# T8105.net
KiCad netlist of a schematic drawn in Altium Designer
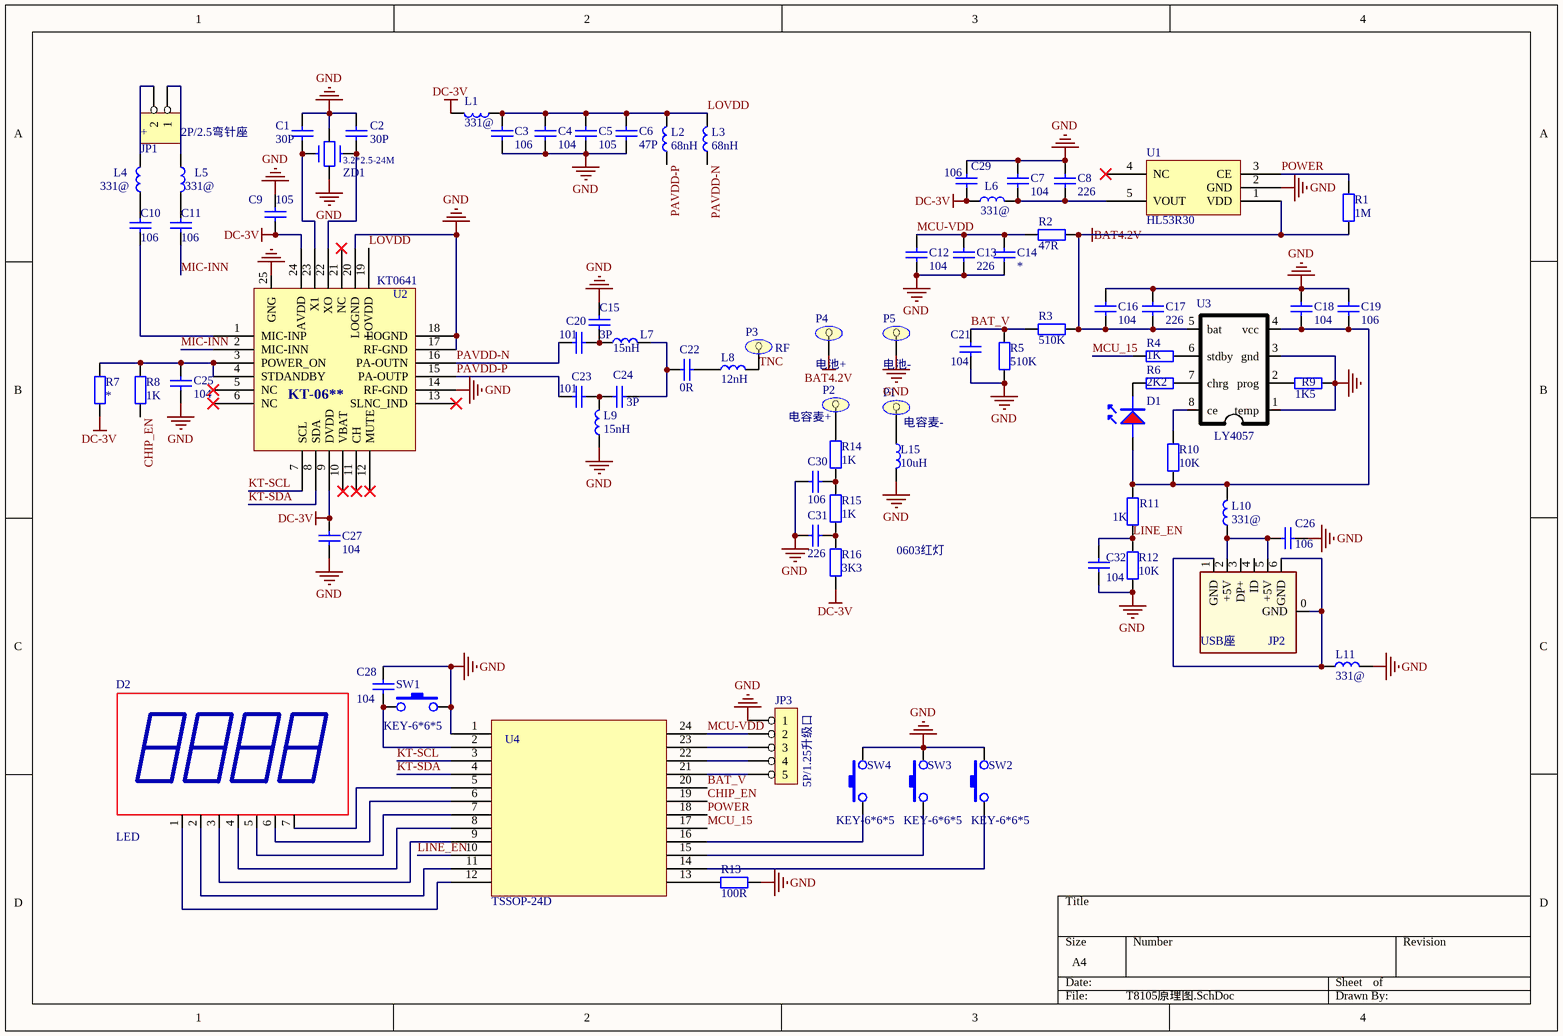
[diagram p0: T8105原理图.SchDoc]

(export (version "E")
  (design (tool "Eeschema 10.0.6"))
  (components
    (comp (ref "C1")
      (value "30P")
      (footprint "C0402")
      (description "贴片电容")
      (libsource (lib "CLR原理图封装库") (part "C0402"))
    )
    (comp (ref "C2")
      (value "30P")
      (footprint "C0402")
      (description "贴片电容")
      (libsource (lib "CLR原理图封装库") (part "C0402"))
    )
    (comp (ref "C3")
      (value "106")
      (footprint "C0603")
      (description "贴片电容")
      (libsource (lib "CLR原理图封装库") (part "C0603"))
    )
    (comp (ref "C4")
      (value "104")
      (footprint "C0402")
      (description "贴片电容")
      (libsource (lib "CLR原理图封装库") (part "C0402"))
    )
    (comp (ref "C5")
      (value "105")
      (footprint "C0402")
      (description "贴片电容")
      (libsource (lib "CLR原理图封装库") (part "C0402"))
    )
    (comp (ref "C6")
      (value "47P")
      (footprint "C0402")
      (description "贴片电容")
      (libsource (lib "CLR原理图封装库") (part "C0402"))
    )
    (comp (ref "C7")
      (value "104")
      (footprint "C0402")
      (description "贴片电容")
      (libsource (lib "CLR原理图封装库") (part "C0402"))
    )
    (comp (ref "C8")
      (value "226")
      (footprint "C0603")
      (description "贴片电容")
      (libsource (lib "CLR原理图封装库") (part "C0603"))
    )
    (comp (ref "C9")
      (value "105")
      (footprint "C0402")
      (description "贴片电容")
      (libsource (lib "CLR原理图封装库") (part "C0402"))
    )
    (comp (ref "C10")
      (value "106")
      (footprint "C0603")
      (description "贴片电容")
      (libsource (lib "CLR原理图封装库") (part "C0603"))
    )
    (comp (ref "C11")
      (value "106")
      (footprint "C0603")
      (description "贴片电容")
      (libsource (lib "CLR原理图封装库") (part "C0603"))
    )
    (comp (ref "C12")
      (value "104")
      (footprint "C0402")
      (description "贴片电容")
      (libsource (lib "CLR原理图封装库") (part "C0402"))
    )
    (comp (ref "C13")
      (value "226")
      (footprint "C0603")
      (description "贴片电容")
      (libsource (lib "CLR原理图封装库") (part "C0603"))
    )
    (comp (ref "C14")
      (value "*")
      (footprint "C1206")
      (description "贴片电容")
      (libsource (lib "CLR原理图封装库") (part "C1206"))
    )
    (comp (ref "C15")
      (value "3P")
      (footprint "C0402")
      (description "贴片电容")
      (libsource (lib "CLR原理图封装库") (part "C0402"))
    )
    (comp (ref "C16")
      (value "104")
      (footprint "C0402")
      (description "贴片电容")
      (libsource (lib "CLR原理图封装库") (part "C0402"))
    )
    (comp (ref "C17")
      (value "226")
      (footprint "C0603")
      (description "贴片电容")
      (libsource (lib "CLR原理图封装库") (part "C0603"))
    )
    (comp (ref "C18")
      (value "104")
      (footprint "C0402")
      (description "贴片电容")
      (libsource (lib "CLR原理图封装库") (part "C0402"))
    )
    (comp (ref "C19")
      (value "106")
      (footprint "C0603")
      (description "贴片电容")
      (libsource (lib "CLR原理图封装库") (part "C0603"))
    )
    (comp (ref "C20")
      (value "101")
      (footprint "C0402")
      (description "贴片电容")
      (libsource (lib "CLR原理图封装库") (part "C0402"))
    )
    (comp (ref "C21")
      (value "104")
      (footprint "C0402")
      (description "贴片电容")
      (libsource (lib "CLR原理图封装库") (part "C0402"))
    )
    (comp (ref "C22")
      (value "0R")
      (footprint "C0402")
      (description "贴片电容")
      (libsource (lib "CLR原理图封装库") (part "C0402"))
    )
    (comp (ref "C23")
      (value "101")
      (footprint "C0402")
      (description "贴片电容")
      (libsource (lib "CLR原理图封装库") (part "C0402"))
    )
    (comp (ref "C24")
      (value "3P")
      (footprint "C0402")
      (description "贴片电容")
      (libsource (lib "CLR原理图封装库") (part "C0402"))
    )
    (comp (ref "C25")
      (value "104")
      (footprint "C0402")
      (description "贴片电容")
      (libsource (lib "CLR原理图封装库") (part "C0402"))
    )
    (comp (ref "C26")
      (value "106")
      (footprint "C0603")
      (description "贴片电容")
      (libsource (lib "CLR原理图封装库") (part "C0603"))
    )
    (comp (ref "C27")
      (value "104")
      (footprint "C0402")
      (description "贴片电容")
      (libsource (lib "CLR原理图封装库") (part "C0402"))
    )
    (comp (ref "C28")
      (value "104")
      (footprint "C0402")
      (description "贴片电容")
      (libsource (lib "CLR原理图封装库") (part "C0402"))
    )
    (comp (ref "C29")
      (value "106")
      (footprint "C0603")
      (description "贴片电容")
      (libsource (lib "CLR原理图封装库") (part "C0603"))
    )
    (comp (ref "C30")
      (value "106")
      (footprint "C0603")
      (description "贴片电容")
      (libsource (lib "CLR原理图封装库") (part "C0603"))
    )
    (comp (ref "C31")
      (value "226")
      (footprint "C0603")
      (description "贴片电容")
      (libsource (lib "CLR原理图封装库") (part "C0603"))
    )
    (comp (ref "C32")
      (value "104")
      (footprint "C0402")
      (description "贴片电容")
      (libsource (lib "CLR原理图封装库") (part "C0402"))
    )
    (comp (ref "D1")
      (value "0603红灯")
      (footprint "LED-0603")
      (description "贴片LED")
      (libsource (lib "CLR原理图封装库") (part "LED-0603"))
    )
    (comp (ref "D2")
      (value "LED")
      (footprint "LED-15*16*7-7pin")
      (description "数码管")
      (libsource (lib "CLR原理图封装库") (part "LED-15*16/数码管"))
    )
    (comp (ref "JP1")
      (value "2P/2.5弯针座")
      (footprint "2P针座-2.54MM_弯针")
      (description "直插针座")
      (libsource (lib "CLR原理图封装库") (part "2P/2.5弯针座"))
    )
    (comp (ref "JP2")
      (value "USB座")
      (footprint "USB-TYPE-C3.1-6")
      (description "直插USB充电座")
      (libsource (lib "CLR原理图封装库") (part "USB-TYPE-C3.1-6"))
    )
    (comp (ref "JP3")
      (value "5P/1.25升级口")
      (footprint "5P插针-12.5MM")
      (description "直插插针")
      (libsource (lib "CLR原理图封装库") (part "5P/1.25插针"))
    )
    (comp (ref "L1")
      (value "331@")
      (footprint "L0402")
      (description "贴片电感")
      (libsource (lib "CLR原理图封装库") (part "L0402"))
    )
    (comp (ref "L2")
      (value "68nH")
      (footprint "L0603")
      (description "贴片电感")
      (libsource (lib "CLR原理图封装库") (part "L0603"))
    )
    (comp (ref "L3")
      (value "68nH")
      (footprint "L0402")
      (description "贴片电感")
      (libsource (lib "CLR原理图封装库") (part "L0402"))
    )
    (comp (ref "L4")
      (value "331@")
      (footprint "L0402")
      (description "贴片电感")
      (libsource (lib "CLR原理图封装库") (part "L0402"))
    )
    (comp (ref "L5")
      (value "331@")
      (footprint "L0402")
      (description "贴片电感")
      (libsource (lib "CLR原理图封装库") (part "L0402"))
    )
    (comp (ref "L6")
      (value "331@")
      (footprint "L0402")
      (description "贴片电感")
      (libsource (lib "CLR原理图封装库") (part "L0402"))
    )
    (comp (ref "L7")
      (value "15nH")
      (footprint "L0402")
      (description "贴片电感")
      (libsource (lib "CLR原理图封装库") (part "L0402"))
    )
    (comp (ref "L8")
      (value "12nH")
      (footprint "L0402")
      (description "贴片电感")
      (libsource (lib "CLR原理图封装库") (part "L0402"))
    )
    (comp (ref "L9")
      (value "15nH")
      (footprint "L0402")
      (description "贴片电感")
      (libsource (lib "CLR原理图封装库") (part "L0402"))
    )
    (comp (ref "L10")
      (value "331@")
      (footprint "L0805")
      (description "贴片电感")
      (libsource (lib "CLR原理图封装库") (part "L0805"))
    )
    (comp (ref "L11")
      (value "331@")
      (footprint "L0805")
      (description "贴片电感")
      (libsource (lib "CLR原理图封装库") (part "L0805"))
    )
    (comp (ref "L15")
      (value "10uH")
      (footprint "L0603")
      (description "贴片电感")
      (libsource (lib "CLR原理图封装库") (part "L0603"))
    )
    (comp (ref "P1")
      (value "电容麦-")
      (footprint "2.2mm焊盘")
      (description "测试焊盘")
      (libsource (lib "CLR原理图封装库") (part "测试焊点"))
    )
    (comp (ref "P2")
      (value "电容麦+")
      (footprint "2.2mm焊盘")
      (description "测试焊盘")
      (libsource (lib "CLR原理图封装库") (part "测试焊点"))
    )
    (comp (ref "P3")
      (value "RF")
      (footprint "2.2mm焊盘")
      (description "测试焊盘")
      (libsource (lib "CLR原理图封装库") (part "测试焊点"))
    )
    (comp (ref "P4")
      (value "电池+")
      (footprint "2.2mm焊盘")
      (description "测试焊盘")
      (libsource (lib "CLR原理图封装库") (part "测试焊点"))
    )
    (comp (ref "P5")
      (value "电池-")
      (footprint "2.2mm焊盘")
      (description "测试焊盘")
      (libsource (lib "CLR原理图封装库") (part "测试焊点"))
    )
    (comp (ref "R1")
      (value "1M")
      (footprint "R0402")
      (description "贴片电阻")
      (libsource (lib "") (part "R0402_1"))
    )
    (comp (ref "R2")
      (value "47R")
      (footprint "R0402")
      (description "贴片电阻")
      (libsource (lib "") (part "R0402_2"))
    )
    (comp (ref "R3")
      (value "510K")
      (footprint "R0402")
      (description "贴片电阻")
      (libsource (lib "") (part "R0402_2"))
    )
    (comp (ref "R4")
      (value "1K")
      (footprint "R0402")
      (description "贴片电阻")
      (libsource (lib "CLR原理图封装库") (part "R0402"))
    )
    (comp (ref "R5")
      (value "510K")
      (footprint "R0402")
      (description "贴片电阻")
      (libsource (lib "") (part "R0402_1"))
    )
    (comp (ref "R6")
      (value "2K2")
      (footprint "R0402")
      (description "贴片电阻")
      (libsource (lib "CLR原理图封装库") (part "R0402"))
    )
    (comp (ref "R7")
      (value "*")
      (footprint "R0402")
      (description "贴片电阻")
      (libsource (lib "") (part "R0402_3"))
    )
    (comp (ref "R8")
      (value "1K")
      (footprint "R0402")
      (description "贴片电阻")
      (libsource (lib "") (part "R0402_1"))
    )
    (comp (ref "R9")
      (value "1K5")
      (footprint "R0402")
      (description "贴片电阻")
      (libsource (lib "") (part "R0402_2"))
    )
    (comp (ref "R10")
      (value "10K")
      (footprint "R0402")
      (description "贴片电阻")
      (libsource (lib "") (part "R0402_1"))
    )
    (comp (ref "R11")
      (value "1K")
      (footprint "R0402")
      (description "贴片电阻")
      (libsource (lib "") (part "R0402_1"))
    )
    (comp (ref "R12")
      (value "10K")
      (footprint "R0402")
      (description "贴片电阻")
      (libsource (lib "") (part "R0402_1"))
    )
    (comp (ref "R13")
      (value "100R")
      (footprint "R0402")
      (description "贴片电阻")
      (libsource (lib "CLR原理图封装库") (part "R0402"))
    )
    (comp (ref "R14")
      (value "1K")
      (footprint "R0402")
      (description "贴片电阻")
      (libsource (lib "") (part "R0402_1"))
    )
    (comp (ref "R15")
      (value "1K")
      (footprint "R0402")
      (description "贴片电阻")
      (libsource (lib "") (part "R0402_1"))
    )
    (comp (ref "R16")
      (value "3K3")
      (footprint "R0402")
      (description "贴片电阻")
      (libsource (lib "") (part "R0402_3"))
    )
    (comp (ref "SW1")
      (value "KEY-6*6*5")
      (footprint "KEY-6*6*5")
      (description "贴片按键")
      (libsource (lib "CLR原理图封装库") (part "KEY-6*6*5"))
    )
    (comp (ref "SW2")
      (value "KEY-6*6*5")
      (footprint "KEY-6*6*5")
      (description "贴片按键")
      (libsource (lib "CLR原理图封装库") (part "KEY-6*6*5"))
    )
    (comp (ref "SW3")
      (value "KEY-6*6*5")
      (footprint "KEY-6*6*5")
      (description "贴片按键")
      (libsource (lib "CLR原理图封装库") (part "KEY-6*6*5"))
    )
    (comp (ref "SW4")
      (value "KEY-6*6*5")
      (footprint "KEY-6*6*5")
      (description "贴片按键")
      (libsource (lib "CLR原理图封装库") (part "KEY-6*6*5"))
    )
    (comp (ref "U1")
      (value "HL53R30")
      (footprint "SOT-23-5")
      (description "贴片三极管")
      (libsource (lib "CLR原理图封装库") (part "SOT-23-5_HL53R33"))
    )
    (comp (ref "U2")
      (value "KT0641")
      (footprint "QFN-24脚-4X4X0.5P")
      (libsource (lib "QFN原理图封装库") (part "QFN-24-4X4X0.5（0642/43）"))
    )
    (comp (ref "U3")
      (value "LY4057")
      (footprint "SOP-8-150")
      (description "充电管理")
      (libsource (lib "CLR原理图封装库") (part "LY4057"))
    )
    (comp (ref "U4")
      (value "TSSOP-24D")
      (footprint "TSSOP-24")
      (description "贴片集成块")
      (libsource (lib "CLR原理图封装库") (part "TSSOP-24"))
    )
    (comp (ref "ZD1")
      (value "3.2*2.5-24M")
      (footprint "SMD-3.2*2.5")
      (description "贴片晶振")
      (libsource (lib "CLR原理图封装库") (part "ZD-3.2*2.5"))
    )
  )
  (nets
    (net (code "1") (name "/BAT_V") (class "Default")
      (node (ref "C21") (pin "2") (pinfunction "2_2") (pintype "passive"))
      (node (ref "R3") (pin "2") (pinfunction "2_2") (pintype "passive"))
      (node (ref "R5") (pin "2") (pinfunction "2_2") (pintype "passive"))
      (node (ref "U4") (pin "20") (pintype "passive"))
    )
    (net (code "2") (name "/CHIP_EN") (class "Default")
      (node (ref "R8") (pin "1") (pinfunction "1_1") (pintype "passive"))
      (node (ref "U4") (pin "19") (pintype "passive"))
    )
    (net (code "3") (name "/KT-SCL") (class "Default")
      (node (ref "U2") (pin "7") (pinfunction "SCL_7") (pintype "passive"))
      (node (ref "U4") (pin "3") (pintype "passive"))
    )
    (net (code "4") (name "/KT-SDA") (class "Default")
      (node (ref "U2") (pin "8") (pinfunction "SDA_8") (pintype "passive"))
      (node (ref "U4") (pin "4") (pintype "passive"))
    )
    (net (code "5") (name "/LINE_EN") (class "Default")
      (node (ref "C32") (pin "2") (pinfunction "2_2") (pintype "passive"))
      (node (ref "R11") (pin "1") (pinfunction "1_1") (pintype "passive"))
      (node (ref "R12") (pin "2") (pinfunction "2_2") (pintype "passive"))
      (node (ref "U4") (pin "10") (pintype "passive"))
    )
    (net (code "6") (name "/LOVDD") (class "Default")
      (node (ref "C3") (pin "1") (pinfunction "1_1") (pintype "passive"))
      (node (ref "C4") (pin "2") (pinfunction "2_2") (pintype "passive"))
      (node (ref "C5") (pin "1") (pinfunction "1_1") (pintype "passive"))
      (node (ref "C6") (pin "1") (pinfunction "1_1") (pintype "passive"))
      (node (ref "L1") (pin "1") (pinfunction "1_1") (pintype "passive"))
      (node (ref "L2") (pin "2") (pinfunction "2_2") (pintype "passive"))
      (node (ref "L3") (pin "2") (pinfunction "2_2") (pintype "passive"))
      (node (ref "U2") (pin "19") (pinfunction "LOVDD_19") (pintype "passive"))
    )
    (net (code "7") (name "/MCU-VDD") (class "Default")
      (node (ref "C12") (pin "2") (pinfunction "2_2") (pintype "passive"))
      (node (ref "C13") (pin "2") (pinfunction "2_2") (pintype "passive"))
      (node (ref "C14") (pin "2") (pinfunction "2_2") (pintype "passive"))
      (node (ref "JP3") (pin "2") (pinfunction "2_2") (pintype "passive"))
      (node (ref "R2") (pin "2") (pinfunction "2_2") (pintype "passive"))
      (node (ref "U4") (pin "24") (pintype "passive"))
    )
    (net (code "8") (name "/MCU_15") (class "Default")
      (node (ref "R4") (pin "1") (pinfunction "1_1") (pintype "passive"))
      (node (ref "U4") (pin "17") (pintype "passive"))
    )
    (net (code "9") (name "/MIC-INN") (class "Default")
      (node (ref "C11") (pin "1") (pinfunction "1_1") (pintype "passive"))
      (node (ref "U2") (pin "2") (pinfunction "MIC-INN_2") (pintype "passive"))
    )
    (net (code "10") (name "/PAVDD-N") (class "Default")
      (node (ref "C20") (pin "2") (pinfunction "2_2") (pintype "passive"))
      (node (ref "L3") (pin "1") (pinfunction "1_1") (pintype "passive"))
      (node (ref "U2") (pin "16") (pinfunction "PA-OUTN_16") (pintype "passive"))
    )
    (net (code "11") (name "/PAVDD-P") (class "Default")
      (node (ref "C23") (pin "2") (pinfunction "2_2") (pintype "passive"))
      (node (ref "L2") (pin "1") (pinfunction "1_1") (pintype "passive"))
      (node (ref "U2") (pin "15") (pinfunction "PA-OUTP_15") (pintype "passive"))
    )
    (net (code "12") (name "/POWER") (class "Default")
      (node (ref "R1") (pin "2") (pinfunction "2_2") (pintype "passive"))
      (node (ref "U1") (pin "3") (pinfunction "CE_3") (pintype "passive"))
      (node (ref "U4") (pin "18") (pintype "passive"))
    )
    (net (code "13") (name "/TNC") (class "Default")
      (node (ref "L8") (pin "2") (pinfunction "2_2") (pintype "passive"))
      (node (ref "P3") (pin "1") (pinfunction "1_1") (pintype "passive"))
    )
    (net (code "14") (name "BAT4.2V") (class "Default")
      (node (ref "C16") (pin "1") (pinfunction "1_1") (pintype "passive"))
      (node (ref "C17") (pin "1") (pinfunction "1_1") (pintype "passive"))
      (node (ref "P4") (pin "1") (pinfunction "1_1") (pintype "passive"))
      (node (ref "R1") (pin "1") (pinfunction "1_1") (pintype "passive"))
      (node (ref "R2") (pin "1") (pinfunction "1_1") (pintype "passive"))
      (node (ref "R3") (pin "1") (pinfunction "1_1") (pintype "passive"))
      (node (ref "U1") (pin "1") (pinfunction "VDD_1") (pintype "passive"))
      (node (ref "U3") (pin "5") (pinfunction "bat_5") (pintype "passive"))
    )
    (net (code "15") (name "DC-3V") (class "Default")
      (node (ref "C27") (pin "2") (pinfunction "2_2") (pintype "passive"))
      (node (ref "C29") (pin "1") (pinfunction "1_1") (pintype "passive"))
      (node (ref "C9") (pin "2") (pinfunction "2_2") (pintype "passive"))
      (node (ref "L1") (pin "2") (pinfunction "2_2") (pintype "passive"))
      (node (ref "L6") (pin "1") (pinfunction "1_1") (pintype "passive"))
      (node (ref "R16") (pin "2") (pinfunction "2_2") (pintype "passive"))
      (node (ref "R7") (pin "2") (pinfunction "2_2") (pintype "passive"))
      (node (ref "U2") (pin "24") (pinfunction "AVDD_24") (pintype "passive"))
      (node (ref "U2") (pin "9") (pinfunction "DVDD_9") (pintype "passive"))
    )
    (net (code "16") (name "GND") (class "Default")
      (node (ref "C1") (pin "2") (pinfunction "2_2") (pintype "passive"))
      (node (ref "C12") (pin "1") (pinfunction "1_1") (pintype "passive"))
      (node (ref "C13") (pin "1") (pinfunction "1_1") (pintype "passive"))
      (node (ref "C14") (pin "1") (pinfunction "1_1") (pintype "passive"))
      (node (ref "C15") (pin "1") (pinfunction "1_1") (pintype "passive"))
      (node (ref "C16") (pin "2") (pinfunction "2_2") (pintype "passive"))
      (node (ref "C17") (pin "2") (pinfunction "2_2") (pintype "passive"))
      (node (ref "C18") (pin "2") (pinfunction "2_2") (pintype "passive"))
      (node (ref "C19") (pin "2") (pinfunction "2_2") (pintype "passive"))
      (node (ref "C2") (pin "2") (pinfunction "2_2") (pintype "passive"))
      (node (ref "C21") (pin "1") (pinfunction "1_1") (pintype "passive"))
      (node (ref "C25") (pin "2") (pinfunction "2_2") (pintype "passive"))
      (node (ref "C26") (pin "2") (pinfunction "2_2") (pintype "passive"))
      (node (ref "C27") (pin "1") (pinfunction "1_1") (pintype "passive"))
      (node (ref "C28") (pin "2") (pinfunction "2_2") (pintype "passive"))
      (node (ref "C29") (pin "2") (pinfunction "2_2") (pintype "passive"))
      (node (ref "C3") (pin "2") (pinfunction "2_2") (pintype "passive"))
      (node (ref "C30") (pin "1") (pinfunction "1_1") (pintype "passive"))
      (node (ref "C31") (pin "1") (pinfunction "1_1") (pintype "passive"))
      (node (ref "C32") (pin "1") (pinfunction "1_1") (pintype "passive"))
      (node (ref "C4") (pin "1") (pinfunction "1_1") (pintype "passive"))
      (node (ref "C5") (pin "2") (pinfunction "2_2") (pintype "passive"))
      (node (ref "C6") (pin "2") (pinfunction "2_2") (pintype "passive"))
      (node (ref "C7") (pin "1") (pinfunction "1_1") (pintype "passive"))
      (node (ref "C8") (pin "2") (pinfunction "2_2") (pintype "passive"))
      (node (ref "C9") (pin "1") (pinfunction "1_1") (pintype "passive"))
      (node (ref "JP3") (pin "1") (pinfunction "1_1") (pintype "passive"))
      (node (ref "L11") (pin "2") (pinfunction "2_2") (pintype "passive"))
      (node (ref "L15") (pin "2") (pinfunction "2_2") (pintype "passive"))
      (node (ref "L9") (pin "1") (pinfunction "1_1") (pintype "passive"))
      (node (ref "P5") (pin "1") (pinfunction "1_1") (pintype "passive"))
      (node (ref "R12") (pin "1") (pinfunction "1_1") (pintype "passive"))
      (node (ref "R13") (pin "2") (pinfunction "2_2") (pintype "passive"))
      (node (ref "R5") (pin "1") (pinfunction "1_1") (pintype "passive"))
      (node (ref "R9") (pin "1") (pinfunction "1_1") (pintype "passive"))
      (node (ref "SW1") (pin "2") (pinfunction "2_2") (pintype "passive"))
      (node (ref "SW2") (pin "2") (pinfunction "2_2") (pintype "passive"))
      (node (ref "SW3") (pin "2") (pinfunction "2_2") (pintype "passive"))
      (node (ref "SW4") (pin "2") (pinfunction "2_2") (pintype "passive"))
      (node (ref "U1") (pin "2") (pinfunction "GND_2") (pintype "passive"))
      (node (ref "U2") (pin "14") (pinfunction "RF-GND_14") (pintype "passive"))
      (node (ref "U2") (pin "17") (pinfunction "RF-GND_17") (pintype "passive"))
      (node (ref "U2") (pin "18") (pinfunction "LOGND_18") (pintype "passive"))
      (node (ref "U2") (pin "20") (pinfunction "LOGND_20") (pintype "passive"))
      (node (ref "U2") (pin "25") (pinfunction "GNG_25") (pintype "passive"))
      (node (ref "U3") (pin "1") (pinfunction "temp_1") (pintype "passive"))
      (node (ref "U3") (pin "3") (pinfunction "gnd_3") (pintype "passive"))
      (node (ref "U4") (pin "1") (pintype "passive"))
      (node (ref "ZD1") (pin "2") (pinfunction "2_2") (pintype "passive"))
      (node (ref "ZD1") (pin "4") (pinfunction "4_4") (pintype "passive"))
    )
    (net (code "17") (name "Net-(C10-Pad2)") (class "Default")
      (node (ref "C10") (pin "2") (pinfunction "2_2") (pintype "passive"))
      (node (ref "L4") (pin "1") (pinfunction "1_1") (pintype "passive"))
    )
    (net (code "18") (name "Net-(C11-Pad2)") (class "Default")
      (node (ref "C11") (pin "2") (pinfunction "2_2") (pintype "passive"))
      (node (ref "L5") (pin "2") (pinfunction "2_2") (pintype "passive"))
    )
    (net (code "19") (name "Net-(C15-Pad2)") (class "Default")
      (node (ref "C15") (pin "2") (pinfunction "2_2") (pintype "passive"))
      (node (ref "C20") (pin "1") (pinfunction "1_1") (pintype "passive"))
      (node (ref "L7") (pin "1") (pinfunction "1_1") (pintype "passive"))
    )
    (net (code "20") (name "Net-(C22-Pad1)") (class "Default")
      (node (ref "C22") (pin "1") (pinfunction "1_1") (pintype "passive"))
      (node (ref "C24") (pin "2") (pinfunction "2_2") (pintype "passive"))
      (node (ref "L7") (pin "2") (pinfunction "2_2") (pintype "passive"))
    )
    (net (code "21") (name "Net-(C22-Pad2)") (class "Default")
      (node (ref "C22") (pin "2") (pinfunction "2_2") (pintype "passive"))
      (node (ref "L8") (pin "1") (pinfunction "1_1") (pintype "passive"))
    )
    (net (code "22") (name "Net-(C23-Pad1)") (class "Default")
      (node (ref "C23") (pin "1") (pinfunction "1_1") (pintype "passive"))
      (node (ref "C24") (pin "1") (pinfunction "1_1") (pintype "passive"))
      (node (ref "L9") (pin "2") (pinfunction "2_2") (pintype "passive"))
    )
    (net (code "23") (name "Net-(C26-Pad1)") (class "Default")
      (node (ref "C26") (pin "1") (pinfunction "1_1") (pintype "passive"))
      (node (ref "JP2") (pin "2") (pinfunction "+5V_2") (pintype "passive"))
      (node (ref "JP2") (pin "5") (pinfunction "+5V_5") (pintype "passive"))
      (node (ref "L10") (pin "1") (pinfunction "1_1") (pintype "passive"))
    )
    (net (code "24") (name "Net-(C28-Pad1)") (class "Default")
      (node (ref "C28") (pin "1") (pinfunction "1_1") (pintype "passive"))
      (node (ref "SW1") (pin "1") (pinfunction "1_1") (pintype "passive"))
      (node (ref "U4") (pin "2") (pintype "passive"))
    )
    (net (code "25") (name "Net-(C30-Pad2)") (class "Default")
      (node (ref "C30") (pin "2") (pinfunction "2_2") (pintype "passive"))
      (node (ref "R14") (pin "1") (pinfunction "1_1") (pintype "passive"))
      (node (ref "R15") (pin "2") (pinfunction "2_2") (pintype "passive"))
    )
    (net (code "26") (name "Net-(C31-Pad2)") (class "Default")
      (node (ref "C31") (pin "2") (pinfunction "2_2") (pintype "passive"))
      (node (ref "R15") (pin "1") (pinfunction "1_1") (pintype "passive"))
      (node (ref "R16") (pin "1") (pinfunction "1_1") (pintype "passive"))
    )
    (net (code "27") (name "Net-(D1-Pad2)") (class "Default")
      (node (ref "D1") (pin "2") (pinfunction "2_2") (pintype "passive"))
      (node (ref "R6") (pin "1") (pinfunction "1_1") (pintype "passive"))
    )
    (net (code "28") (name "Net-(D2-Pad1)") (class "Default")
      (node (ref "D2") (pin "1") (pintype "passive"))
      (node (ref "U4") (pin "12") (pintype "passive"))
    )
    (net (code "29") (name "Net-(D2-Pad2)") (class "Default")
      (node (ref "D2") (pin "2") (pintype "passive"))
      (node (ref "U4") (pin "11") (pintype "passive"))
    )
    (net (code "30") (name "Net-(D2-Pad3)") (class "Default")
      (node (ref "D2") (pin "3") (pintype "passive"))
      (node (ref "U4") (pin "9") (pintype "passive"))
    )
    (net (code "31") (name "Net-(D2-Pad4)") (class "Default")
      (node (ref "D2") (pin "4") (pintype "passive"))
      (node (ref "U4") (pin "8") (pintype "passive"))
    )
    (net (code "32") (name "Net-(D2-Pad5)") (class "Default")
      (node (ref "D2") (pin "5") (pintype "passive"))
      (node (ref "U4") (pin "7") (pintype "passive"))
    )
    (net (code "33") (name "Net-(D2-Pad6)") (class "Default")
      (node (ref "D2") (pin "6") (pintype "passive"))
      (node (ref "U4") (pin "6") (pintype "passive"))
    )
    (net (code "34") (name "Net-(D2-Pad7)") (class "Default")
      (node (ref "D2") (pin "7") (pintype "passive"))
      (node (ref "U4") (pin "5") (pintype "passive"))
    )
    (net (code "35") (name "Net-(JP1-Pad1)") (class "Default")
      (node (ref "JP1") (pin "1") (pinfunction "1_1") (pintype "passive"))
      (node (ref "L5") (pin "1") (pinfunction "1_1") (pintype "passive"))
    )
    (net (code "36") (name "Net-(JP1-Pad2)") (class "Default")
      (node (ref "JP1") (pin "2") (pinfunction "2_2") (pintype "passive"))
      (node (ref "L4") (pin "2") (pinfunction "2_2") (pintype "passive"))
    )
    (net (code "37") (name "Net-(JP2-GND-Pad0)") (class "Default")
      (node (ref "JP2") (pin "0") (pinfunction "GND_0") (pintype "passive"))
      (node (ref "JP2") (pin "1") (pinfunction "GND_1") (pintype "passive"))
      (node (ref "JP2") (pin "6") (pinfunction "GND_6") (pintype "passive"))
      (node (ref "L11") (pin "1") (pinfunction "1_1") (pintype "passive"))
    )
    (net (code "38") (name "Net-(JP3-Pad3)") (class "Default")
      (node (ref "JP3") (pin "3") (pinfunction "3_3") (pintype "passive"))
      (node (ref "U4") (pin "23") (pintype "passive"))
    )
    (net (code "39") (name "Net-(JP3-Pad4)") (class "Default")
      (node (ref "JP3") (pin "4") (pinfunction "4_4") (pintype "passive"))
      (node (ref "U4") (pin "22") (pintype "passive"))
    )
    (net (code "40") (name "Net-(JP3-Pad5)") (class "Default")
      (node (ref "JP3") (pin "5") (pinfunction "5_5") (pintype "passive"))
      (node (ref "U4") (pin "21") (pintype "passive"))
    )
    (net (code "41") (name "Net-(L15-Pad1)") (class "Default")
      (node (ref "L15") (pin "1") (pinfunction "1_1") (pintype "passive"))
      (node (ref "P1") (pin "1") (pinfunction "1_1") (pintype "passive"))
    )
    (net (code "42") (name "Net-(P2-Pad1)") (class "Default")
      (node (ref "P2") (pin "1") (pinfunction "1_1") (pintype "passive"))
      (node (ref "R14") (pin "2") (pinfunction "2_2") (pintype "passive"))
    )
    (net (code "43") (name "Net-(R13-Pad1)") (class "Default")
      (node (ref "R13") (pin "1") (pinfunction "1_1") (pintype "passive"))
      (node (ref "U4") (pin "13") (pintype "passive"))
    )
    (net (code "44") (name "Net-(SW2-Pad1)") (class "Default")
      (node (ref "SW2") (pin "1") (pinfunction "1_1") (pintype "passive"))
      (node (ref "U4") (pin "14") (pintype "passive"))
    )
    (net (code "45") (name "Net-(SW3-Pad1)") (class "Default")
      (node (ref "SW3") (pin "1") (pinfunction "1_1") (pintype "passive"))
      (node (ref "U4") (pin "15") (pintype "passive"))
    )
    (net (code "46") (name "Net-(SW4-Pad1)") (class "Default")
      (node (ref "SW4") (pin "1") (pinfunction "1_1") (pintype "passive"))
      (node (ref "U4") (pin "16") (pintype "passive"))
    )
    (net (code "47") (name "Net-(U1-VOUT)") (class "Default")
      (node (ref "C7") (pin "2") (pinfunction "2_2") (pintype "passive"))
      (node (ref "C8") (pin "1") (pinfunction "1_1") (pintype "passive"))
      (node (ref "L6") (pin "2") (pinfunction "2_2") (pintype "passive"))
      (node (ref "U1") (pin "5") (pinfunction "VOUT_5") (pintype "passive"))
    )
    (net (code "48") (name "Net-(U2-MIC-INP)") (class "Default")
      (node (ref "C10") (pin "1") (pinfunction "1_1") (pintype "passive"))
      (node (ref "U2") (pin "1") (pinfunction "MIC-INP_1") (pintype "passive"))
    )
    (net (code "49") (name "Net-(U2-POWER_ON)") (class "Default")
      (node (ref "C25") (pin "1") (pinfunction "1_1") (pintype "passive"))
      (node (ref "R7") (pin "1") (pinfunction "1_1") (pintype "passive"))
      (node (ref "R8") (pin "2") (pinfunction "2_2") (pintype "passive"))
      (node (ref "U2") (pin "3") (pinfunction "POWER_ON_3") (pintype "passive"))
      (node (ref "U2") (pin "4") (pinfunction "STDANDBY_4") (pintype "passive"))
    )
    (net (code "50") (name "Net-(U2-X1)") (class "Default")
      (node (ref "C1") (pin "1") (pinfunction "1_1") (pintype "passive"))
      (node (ref "U2") (pin "23") (pinfunction "X1_23") (pintype "passive"))
      (node (ref "ZD1") (pin "1") (pinfunction "1_1") (pintype "passive"))
    )
    (net (code "51") (name "Net-(U2-XO)") (class "Default")
      (node (ref "C2") (pin "1") (pinfunction "1_1") (pintype "passive"))
      (node (ref "U2") (pin "22") (pinfunction "XO_22") (pintype "passive"))
      (node (ref "ZD1") (pin "3") (pinfunction "3_3") (pintype "passive"))
    )
    (net (code "52") (name "Net-(U3-ce)") (class "Default")
      (node (ref "R10") (pin "2") (pinfunction "2_2") (pintype "passive"))
      (node (ref "U3") (pin "8") (pinfunction "ce_8") (pintype "passive"))
    )
    (net (code "53") (name "Net-(U3-chrg)") (class "Default")
      (node (ref "R6") (pin "2") (pinfunction "2_2") (pintype "passive"))
      (node (ref "U3") (pin "7") (pinfunction "chrg_7") (pintype "passive"))
    )
    (net (code "54") (name "Net-(U3-prog)") (class "Default")
      (node (ref "R9") (pin "2") (pinfunction "2_2") (pintype "passive"))
      (node (ref "U3") (pin "2") (pinfunction "prog_2") (pintype "passive"))
    )
    (net (code "55") (name "Net-(U3-stdby)") (class "Default")
      (node (ref "R4") (pin "2") (pinfunction "2_2") (pintype "passive"))
      (node (ref "U3") (pin "6") (pinfunction "stdby_6") (pintype "passive"))
    )
    (net (code "56") (name "Net-(U3-vcc)") (class "Default")
      (node (ref "C18") (pin "1") (pinfunction "1_1") (pintype "passive"))
      (node (ref "C19") (pin "1") (pinfunction "1_1") (pintype "passive"))
      (node (ref "D1") (pin "1") (pinfunction "1_1") (pintype "passive"))
      (node (ref "L10") (pin "2") (pinfunction "2_2") (pintype "passive"))
      (node (ref "R10") (pin "1") (pinfunction "1_1") (pintype "passive"))
      (node (ref "R11") (pin "2") (pinfunction "2_2") (pintype "passive"))
      (node (ref "U3") (pin "4") (pinfunction "vcc_4") (pintype "passive"))
    )
    (net (code "57") (name "unconnected-(JP2-DP+-Pad3)") (class "Default")
      (node (ref "JP2") (pin "3") (pinfunction "DP+_3") (pintype "passive"))
    )
    (net (code "58") (name "unconnected-(JP2-ID-Pad4)") (class "Default")
      (node (ref "JP2") (pin "4") (pinfunction "ID_4") (pintype "passive"))
    )
    (net (code "59") (name "unconnected-(U1-NC-Pad4)") (class "Default")
      (node (ref "U1") (pin "4") (pinfunction "NC_4") (pintype "passive+no_connect"))
    )
    (net (code "60") (name "unconnected-(U2-CH-Pad11)") (class "Default")
      (node (ref "U2") (pin "11") (pinfunction "CH_11") (pintype "passive+no_connect"))
    )
    (net (code "61") (name "unconnected-(U2-MUTE-Pad12)") (class "Default")
      (node (ref "U2") (pin "12") (pinfunction "MUTE_12") (pintype "passive+no_connect"))
    )
    (net (code "62") (name "unconnected-(U2-NC-Pad5)") (class "Default")
      (node (ref "U2") (pin "5") (pinfunction "NC_5") (pintype "passive+no_connect"))
    )
    (net (code "63") (name "unconnected-(U2-NC-Pad6)") (class "Default")
      (node (ref "U2") (pin "6") (pinfunction "NC_6") (pintype "passive+no_connect"))
    )
    (net (code "64") (name "unconnected-(U2-NC-Pad21)") (class "Default")
      (node (ref "U2") (pin "21") (pinfunction "NC_21") (pintype "passive+no_connect"))
    )
    (net (code "65") (name "unconnected-(U2-SLNC_IND-Pad13)") (class "Default")
      (node (ref "U2") (pin "13") (pinfunction "SLNC_IND_13") (pintype "passive+no_connect"))
    )
    (net (code "66") (name "unconnected-(U2-VBAT-Pad10)") (class "Default")
      (node (ref "U2") (pin "10") (pinfunction "VBAT_10") (pintype "passive+no_connect"))
    )
  )
)
